# sapflow_v5.net
KiCad netlist of a schematic drawn in EAGLE
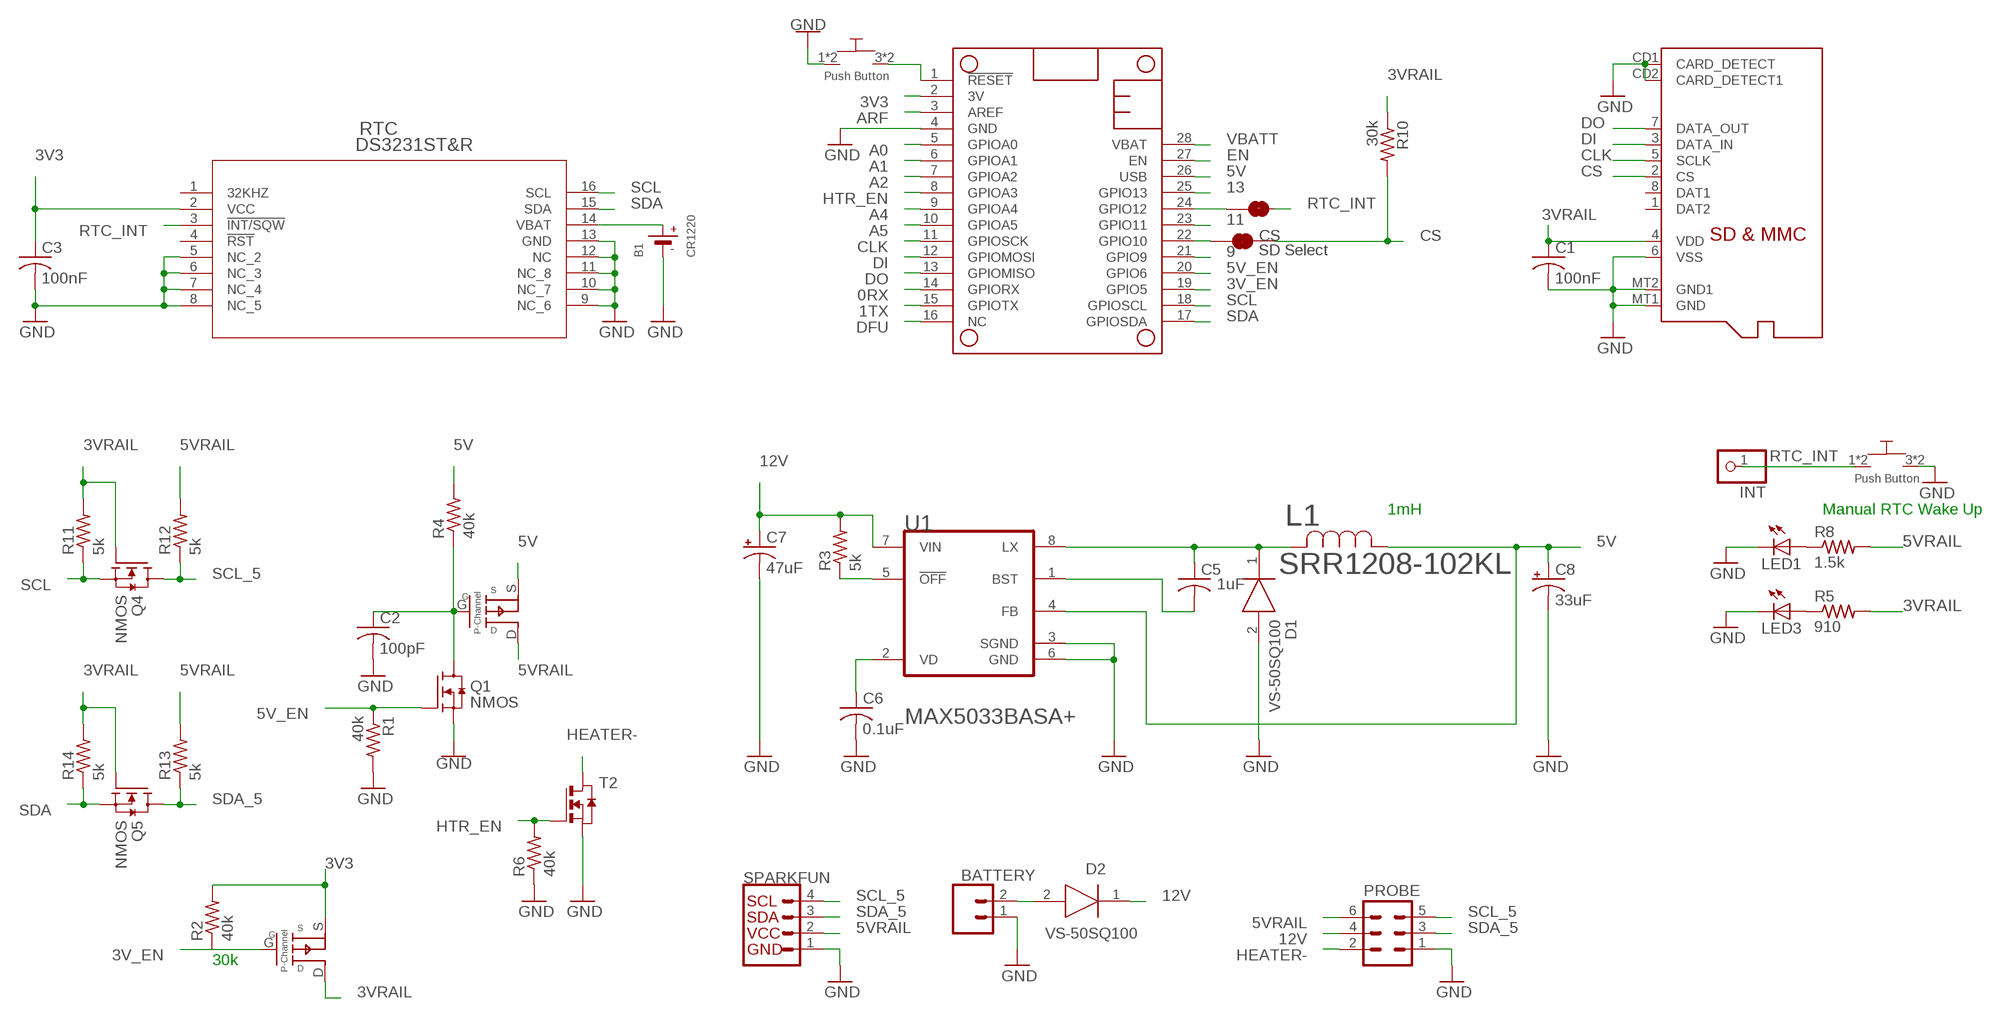
[diagram p0: schematic, sheet 1]

(export (version "E")
  (design (tool "Eeschema 10.0.6"))
  (components
    (comp (ref "B1")
      (value "CR1220")
      (footprint "eagle-import:CR1220")
      (libsource (lib "eagle-import") (part "BATTERYCR1220_SMT"))
    )
    (comp (ref "BATTERY")
      (value "HIGHV-OUT")
      (footprint "eagle-import:1X02_NO_SILK")
      (libsource (lib "eagle-import") (part "CONN_021X02_NO_SILK"))
    )
    (comp (ref "C1")
      (value "100nF")
      (footprint "eagle-import:C0805")
      (libsource (lib "eagle-import") (part "C-USC0805"))
    )
    (comp (ref "C2")
      (value "100pF")
      (footprint "eagle-import:C0805")
      (libsource (lib "eagle-import") (part "resistor_348_C-USC0805"))
    )
    (comp (ref "C3")
      (value "100nF")
      (footprint "eagle-import:C0805")
      (libsource (lib "eagle-import") (part "C-USC0805"))
    )
    (comp (ref "C5")
      (value "1uF")
      (footprint "eagle-import:C0805")
      (libsource (lib "eagle-import") (part "rcl_334_C-USC0805"))
    )
    (comp (ref "C6")
      (value "0.1uF")
      (footprint "eagle-import:C0805")
      (libsource (lib "eagle-import") (part "rcl_334_C-USC0805"))
    )
    (comp (ref "C7")
      (value "47uF")
      (footprint "eagle-import:D_7343-31R")
      (libsource (lib "eagle-import") (part "CPOL-USD/7343-31R"))
    )
    (comp (ref "C8")
      (value "33uF")
      (footprint "eagle-import:D_7343-31R")
      (libsource (lib "eagle-import") (part "CPOL-USD/7343-31R"))
    )
    (comp (ref "CS")
      (value "SD Select")
      (footprint "eagle-import:SMT-JUMPER_2_NC_TRACE_SILK")
      (libsource (lib "eagle-import") (part "JUMPER-SMT_2_NC_TRACE_SILK"))
    )
    (comp (ref "D1")
      (value "VS-50SQ100")
      (footprint "eagle-import:DIOAD1405W86L465D235")
      (fields (field (name "MOUSER_PART_NUMBER") "844-50SQ100") (field (name "RS_PART_NUMBER") "5446041"))
      (libsource (lib "eagle-import") (part "VS-50SQ100"))
    )
    (comp (ref "D2")
      (value "VS-50SQ100")
      (footprint "eagle-import:DIOAD1405W86L465D235")
      (fields (field (name "MOUSER_PART_NUMBER") "844-50SQ100") (field (name "RS_PART_NUMBER") "5446041"))
      (libsource (lib "eagle-import") (part "VS-50SQ100"))
    )
    (comp (ref "INT")
      (value "PINHD-1X1CB")
      (footprint "eagle-import:1X01-CLEANBIG")
      (libsource (lib "eagle-import") (part "PINHD-1X1CB"))
    )
    (comp (ref "L1")
      (value "SRR1208-102KL")
      (footprint "eagle-import:IND_BOURNS_SRR1208")
      (libsource (lib "eagle-import") (part "SRR1208-102KL"))
    )
    (comp (ref "LED1")
      (value "RED")
      (footprint "eagle-import:CHIPLED_0805")
      (libsource (lib "eagle-import") (part "LEDCHIPLED_0805"))
    )
    (comp (ref "LED3")
      (value "RED")
      (footprint "eagle-import:CHIPLED_0805")
      (libsource (lib "eagle-import") (part "LEDCHIPLED_0805"))
    )
    (comp (ref "MICROSD")
      (value "MICROSD")
      (footprint "eagle-import:MICROSD")
      (libsource (lib "eagle-import") (part "MICROSD"))
    )
    (comp (ref "MS2")
      (value "FEATHERWING")
      (footprint "eagle-import:FEATHERWING")
      (libsource (lib "eagle-import") (part "FEATHERWING"))
    )
    (comp (ref "PMOS1")
      (value "SSM3J3228R")
      (footprint "eagle-import:SOT-23-3")
      (libsource (lib "eagle-import") (part "SSM3J3228R"))
    )
    (comp (ref "PMOS2")
      (value "SSM3J3228R")
      (footprint "eagle-import:SOT-23-3")
      (libsource (lib "eagle-import") (part "SSM3J3228R"))
    )
    (comp (ref "PROBE")
      (value "MA03-2")
      (footprint "eagle-import:MA03-2")
      (libsource (lib "eagle-import") (part "MA03-2"))
    )
    (comp (ref "Q1")
      (value "NMOS")
      (footprint "eagle-import:SOT23-S")
      (libsource (lib "eagle-import") (part "NMOS"))
    )
    (comp (ref "Q4")
      (value "NMOS")
      (footprint "eagle-import:SOT23-S")
      (libsource (lib "eagle-import") (part "NMOS"))
    )
    (comp (ref "Q5")
      (value "NMOS")
      (footprint "eagle-import:SOT23-S")
      (libsource (lib "eagle-import") (part "NMOS"))
    )
    (comp (ref "R1")
      (value "40k")
      (footprint "eagle-import:R0805")
      (libsource (lib "eagle-import") (part "R-US_R0805"))
    )
    (comp (ref "R2")
      (value "40k")
      (footprint "eagle-import:R0805")
      (libsource (lib "eagle-import") (part "R-US_R0805"))
    )
    (comp (ref "R3")
      (value "5k")
      (footprint "eagle-import:R0805")
      (libsource (lib "eagle-import") (part "R-US_R0805"))
    )
    (comp (ref "R4")
      (value "40k")
      (footprint "eagle-import:R0805")
      (libsource (lib "eagle-import") (part "R-US_R0805"))
    )
    (comp (ref "R5")
      (value "910")
      (footprint "eagle-import:R0805")
      (libsource (lib "eagle-import") (part "R-US_R0805"))
    )
    (comp (ref "R6")
      (value "40k")
      (footprint "eagle-import:R0805")
      (libsource (lib "eagle-import") (part "R-US_R0805"))
    )
    (comp (ref "R8")
      (value "1.5k")
      (footprint "eagle-import:R0805")
      (libsource (lib "eagle-import") (part "R-US_R0805"))
    )
    (comp (ref "R10")
      (value "30k")
      (footprint "eagle-import:R0805")
      (libsource (lib "eagle-import") (part "R-US_R0805"))
    )
    (comp (ref "R11")
      (value "5k")
      (footprint "eagle-import:R0805")
      (libsource (lib "eagle-import") (part "R-US_R0805"))
    )
    (comp (ref "R12")
      (value "5k")
      (footprint "eagle-import:R0805")
      (libsource (lib "eagle-import") (part "R-US_R0805"))
    )
    (comp (ref "R13")
      (value "5k")
      (footprint "eagle-import:R0805")
      (libsource (lib "eagle-import") (part "R-US_R0805"))
    )
    (comp (ref "R14")
      (value "5k")
      (footprint "eagle-import:R0805")
      (libsource (lib "eagle-import") (part "R-US_R0805"))
    )
    (comp (ref "RTC")
      (value "DS3231ST&R")
      (footprint "eagle-import:21-0042B_16")
      (fields (field (name "MANUFACTURER_PART_NUMBER") "DS3231S#T&R"))
      (libsource (lib "eagle-import") (part "DS3231ST&R"))
    )
    (comp (ref "RTC_INT")
      (value "JUMPER-SMT_2_NC_TRACE_SILK")
      (footprint "eagle-import:SMT-JUMPER_2_NC_TRACE_SILK")
      (libsource (lib "eagle-import") (part "JUMPER-SMT_2_NC_TRACE_SILK"))
    )
    (comp (ref "SPARKFUN")
      (value "I2C_STANDARD_NO_SILK")
      (footprint "eagle-import:1X04_NO_SILK")
      (libsource (lib "eagle-import") (part "I2C_STANDARD_NO_SILK"))
    )
    (comp (ref "T2")
      (value "NMOSSOT223")
      (footprint "eagle-import:SOT223")
      (libsource (lib "eagle-import") (part "NMOSSOT223"))
    )
    (comp (ref "U$1")
      (value "PUSH_BUTTON")
      (footprint "eagle-import:PUSHBUTTON_SMD")
      (libsource (lib "eagle-import") (part "PUSH_BUTTON"))
    )
    (comp (ref "U$2")
      (value "PUSH_BUTTON")
      (footprint "eagle-import:PUSHBUTTON_SMD")
      (libsource (lib "eagle-import") (part "PUSH_BUTTON"))
    )
    (comp (ref "U1")
      (value "MAXIM_MAX5033BASA+MAXIM_MAX5033BASA+_0_1")
      (footprint "eagle-import:MAXIM_MAX5033BASA+_1")
      (fields (field (name "MF") "Maxim") (field (name "MPN") "MAX5033BASA+"))
      (libsource (lib "eagle-import") (part "MAXIM_MAX5033BASA+MAXIM_MAX5033BASA+_0_1"))
    )
  )
  (nets
    (net (code "1") (name "/0RX") (class "Default")
      (node (ref "MS2") (pin "14") (pinfunction "GPIORX_14") (pintype "bidirectional"))
    )
    (net (code "2") (name "/1TX") (class "Default")
      (node (ref "MS2") (pin "15") (pinfunction "GPIOTX_15") (pintype "bidirectional"))
    )
    (net (code "3") (name "/3V3") (class "Default")
      (node (ref "C3") (pin "1") (pinfunction "1_1") (pintype "passive"))
      (node (ref "MS2") (pin "2") (pinfunction "3V_2") (pintype "power_in"))
      (node (ref "PMOS2") (pin "S") (pinfunction "S_S") (pintype "bidirectional"))
      (node (ref "R2") (pin "2") (pinfunction "2_2") (pintype "passive"))
      (node (ref "RTC") (pin "2") (pinfunction "VCC_2") (pintype "power_in"))
    )
    (net (code "4") (name "/3VRAIL") (class "Default")
      (node (ref "C1") (pin "1") (pinfunction "1_1") (pintype "passive"))
      (node (ref "MICROSD") (pin "4") (pinfunction "VDD_4") (pintype "power_in"))
      (node (ref "PMOS2") (pin "D") (pinfunction "D_D") (pintype "bidirectional"))
      (node (ref "Q4") (pin "1") (pinfunction "G_1") (pintype "passive"))
      (node (ref "Q5") (pin "1") (pinfunction "G_1") (pintype "passive"))
      (node (ref "R10") (pin "1") (pinfunction "1_1") (pintype "passive"))
      (node (ref "R11") (pin "2") (pinfunction "2_2") (pintype "passive"))
      (node (ref "R14") (pin "2") (pinfunction "2_2") (pintype "passive"))
      (node (ref "R5") (pin "2") (pinfunction "2_2") (pintype "passive"))
    )
    (net (code "5") (name "/3V_EN") (class "Default")
      (node (ref "MS2") (pin "19") (pinfunction "GPIO5_19") (pintype "bidirectional"))
      (node (ref "PMOS2") (pin "G") (pinfunction "G_G") (pintype "bidirectional"))
      (node (ref "R2") (pin "1") (pinfunction "1_1") (pintype "passive"))
    )
    (net (code "6") (name "/5V") (class "Default")
      (node (ref "C8") (pin "+") (pinfunction "+_+") (pintype "passive"))
      (node (ref "L1") (pin "1") (pinfunction "1_1") (pintype "passive"))
      (node (ref "MS2") (pin "26") (pinfunction "USB_26") (pintype "power_in"))
      (node (ref "PMOS1") (pin "S") (pinfunction "S_S") (pintype "bidirectional"))
      (node (ref "R4") (pin "2") (pinfunction "2_2") (pintype "passive"))
      (node (ref "U1") (pin "4") (pinfunction "FB_4") (pintype "input"))
    )
    (net (code "7") (name "/5VRAIL") (class "Default")
      (node (ref "PMOS1") (pin "D") (pinfunction "D_D") (pintype "bidirectional"))
      (node (ref "PROBE") (pin "6") (pinfunction "6_6") (pintype "passive"))
      (node (ref "R12") (pin "2") (pinfunction "2_2") (pintype "passive"))
      (node (ref "R13") (pin "2") (pinfunction "2_2") (pintype "passive"))
      (node (ref "R8") (pin "2") (pinfunction "2_2") (pintype "passive"))
      (node (ref "SPARKFUN") (pin "2") (pinfunction "VCC_2") (pintype "power_in"))
    )
    (net (code "8") (name "/5V_EN") (class "Default")
      (node (ref "MS2") (pin "20") (pinfunction "GPIO6_20") (pintype "bidirectional"))
      (node (ref "Q1") (pin "1") (pinfunction "G_1") (pintype "passive"))
      (node (ref "R1") (pin "1") (pinfunction "1_1") (pintype "passive"))
    )
    (net (code "9") (name "/9") (class "Default")
      (node (ref "MS2") (pin "21") (pinfunction "GPIO9_21") (pintype "bidirectional"))
    )
    (net (code "10") (name "/11") (class "Default")
      (node (ref "MS2") (pin "23") (pinfunction "GPIO11_23") (pintype "bidirectional"))
    )
    (net (code "11") (name "/12V") (class "Default")
      (node (ref "C7") (pin "+") (pinfunction "+_+") (pintype "passive"))
      (node (ref "D2") (pin "1") (pinfunction "K_1") (pintype "bidirectional"))
      (node (ref "PROBE") (pin "4") (pinfunction "4_4") (pintype "passive"))
      (node (ref "R3") (pin "2") (pinfunction "2_2") (pintype "passive"))
      (node (ref "U1") (pin "7") (pinfunction "VIN_7") (pintype "power_in"))
    )
    (net (code "12") (name "/13") (class "Default")
      (node (ref "MS2") (pin "25") (pinfunction "GPIO13_25") (pintype "bidirectional"))
    )
    (net (code "13") (name "/A0") (class "Default")
      (node (ref "MS2") (pin "5") (pinfunction "GPIOA0_5") (pintype "bidirectional"))
    )
    (net (code "14") (name "/A1") (class "Default")
      (node (ref "MS2") (pin "6") (pinfunction "GPIOA1_6") (pintype "bidirectional"))
    )
    (net (code "15") (name "/A2") (class "Default")
      (node (ref "MS2") (pin "7") (pinfunction "GPIOA2_7") (pintype "bidirectional"))
    )
    (net (code "16") (name "/A4") (class "Default")
      (node (ref "MS2") (pin "9") (pinfunction "GPIOA4_9") (pintype "bidirectional"))
    )
    (net (code "17") (name "/A5") (class "Default")
      (node (ref "MS2") (pin "10") (pinfunction "GPIOA5_10") (pintype "bidirectional"))
    )
    (net (code "18") (name "/ARF") (class "Default")
      (node (ref "MS2") (pin "3") (pinfunction "AREF_3") (pintype "passive"))
    )
    (net (code "19") (name "/CLK") (class "Default")
      (node (ref "MICROSD") (pin "5") (pinfunction "SCLK_5") (pintype "input"))
      (node (ref "MS2") (pin "11") (pinfunction "GPIOSCK_11") (pintype "bidirectional"))
    )
    (net (code "20") (name "/CS") (class "Default")
      (node (ref "CS") (pin "2") (pinfunction "2_2") (pintype "passive"))
      (node (ref "MICROSD") (pin "2") (pinfunction "CS_2") (pintype "input"))
      (node (ref "R10") (pin "2") (pinfunction "2_2") (pintype "passive"))
    )
    (net (code "21") (name "/DFU") (class "Default")
      (node (ref "MS2") (pin "16") (pinfunction "NC_16") (pintype "passive"))
    )
    (net (code "22") (name "/DI") (class "Default")
      (node (ref "MICROSD") (pin "3") (pinfunction "DATA_IN_3") (pintype "input"))
      (node (ref "MS2") (pin "12") (pinfunction "GPIOMOSI_12") (pintype "bidirectional"))
    )
    (net (code "23") (name "/DO") (class "Default")
      (node (ref "MICROSD") (pin "7") (pinfunction "DATA_OUT_7") (pintype "output"))
      (node (ref "MS2") (pin "13") (pinfunction "GPIOMISO_13") (pintype "bidirectional"))
    )
    (net (code "24") (name "/EN") (class "Default")
      (node (ref "MS2") (pin "27") (pinfunction "EN_27") (pintype "passive"))
    )
    (net (code "25") (name "/HEATER-") (class "Default")
      (node (ref "PROBE") (pin "2") (pinfunction "2_2") (pintype "passive"))
      (node (ref "T2") (pin "2") (pinfunction "D_2") (pintype "passive"))
      (node (ref "T2") (pin "4") (pinfunction "D_4") (pintype "passive"))
    )
    (net (code "26") (name "/HTR_EN") (class "Default")
      (node (ref "MS2") (pin "8") (pinfunction "GPIOA3_8") (pintype "bidirectional"))
      (node (ref "R6") (pin "2") (pinfunction "2_2") (pintype "passive"))
      (node (ref "T2") (pin "1") (pinfunction "G_1") (pintype "passive"))
    )
    (net (code "27") (name "/RTC_INT") (class "Default")
      (node (ref "INT") (pin "1") (pinfunction "1_1") (pintype "passive"))
      (node (ref "RTC") (pin "3") (pinfunction "~{INT/SQW}_3") (pintype "passive"))
      (node (ref "RTC_INT") (pin "2") (pinfunction "2_2") (pintype "passive"))
      (node (ref "U$2") (pin "1") (pinfunction "P$1_1") (pintype "bidirectional"))
      (node (ref "U$2") (pin "2") (pinfunction "P$1_2") (pintype "bidirectional"))
    )
    (net (code "28") (name "/SCL") (class "Default")
      (node (ref "MS2") (pin "18") (pinfunction "GPIOSCL_18") (pintype "bidirectional"))
      (node (ref "Q4") (pin "2") (pinfunction "S_2") (pintype "passive"))
      (node (ref "R11") (pin "1") (pinfunction "1_1") (pintype "passive"))
      (node (ref "RTC") (pin "16") (pinfunction "SCL_16") (pintype "passive"))
    )
    (net (code "29") (name "/SCL_5") (class "Default")
      (node (ref "PROBE") (pin "5") (pinfunction "5_5") (pintype "passive"))
      (node (ref "Q4") (pin "3") (pinfunction "D_3") (pintype "passive"))
      (node (ref "R12") (pin "1") (pinfunction "1_1") (pintype "passive"))
      (node (ref "SPARKFUN") (pin "4") (pinfunction "SCL_4") (pintype "passive"))
    )
    (net (code "30") (name "/SDA") (class "Default")
      (node (ref "MS2") (pin "17") (pinfunction "GPIOSDA_17") (pintype "bidirectional"))
      (node (ref "Q5") (pin "2") (pinfunction "S_2") (pintype "passive"))
      (node (ref "R14") (pin "1") (pinfunction "1_1") (pintype "passive"))
      (node (ref "RTC") (pin "15") (pinfunction "SDA_15") (pintype "passive"))
    )
    (net (code "31") (name "/SDA_5") (class "Default")
      (node (ref "PROBE") (pin "3") (pinfunction "3_3") (pintype "passive"))
      (node (ref "Q5") (pin "3") (pinfunction "D_3") (pintype "passive"))
      (node (ref "R13") (pin "1") (pinfunction "1_1") (pintype "passive"))
      (node (ref "SPARKFUN") (pin "3") (pinfunction "SDA_3") (pintype "passive"))
    )
    (net (code "32") (name "/VBATT") (class "Default")
      (node (ref "MS2") (pin "28") (pinfunction "VBAT_28") (pintype "power_in"))
    )
    (net (code "33") (name "GND") (class "Default")
      (node (ref "B1") (pin "-") (pinfunction "-_-") (pintype "passive"))
      (node (ref "BATTERY") (pin "1") (pinfunction "1_1") (pintype "passive"))
      (node (ref "C1") (pin "2") (pinfunction "2_2") (pintype "passive"))
      (node (ref "C2") (pin "2") (pinfunction "2_2") (pintype "passive"))
      (node (ref "C3") (pin "2") (pinfunction "2_2") (pintype "passive"))
      (node (ref "C6") (pin "2") (pinfunction "2_2") (pintype "passive"))
      (node (ref "C7") (pin "-") (pinfunction "-_-") (pintype "passive"))
      (node (ref "C8") (pin "-") (pinfunction "-_-") (pintype "passive"))
      (node (ref "D1") (pin "2") (pinfunction "A_2") (pintype "bidirectional"))
      (node (ref "LED1") (pin "C") (pinfunction "C_C") (pintype "passive"))
      (node (ref "LED3") (pin "C") (pinfunction "C_C") (pintype "passive"))
      (node (ref "MICROSD") (pin "6") (pinfunction "VSS_6") (pintype "power_in"))
      (node (ref "MICROSD") (pin "CD1") (pinfunction "CARD_DETECT_CD1") (pintype "passive"))
      (node (ref "MICROSD") (pin "CD2") (pinfunction "CARD_DETECT1_CD2") (pintype "passive"))
      (node (ref "MICROSD") (pin "MT1") (pinfunction "GND_MT1") (pintype "power_in"))
      (node (ref "MICROSD") (pin "MT2") (pinfunction "GND1_MT2") (pintype "power_in"))
      (node (ref "MS2") (pin "4") (pinfunction "GND_4") (pintype "power_in"))
      (node (ref "PROBE") (pin "1") (pinfunction "1_1") (pintype "passive"))
      (node (ref "Q1") (pin "2") (pinfunction "S_2") (pintype "passive"))
      (node (ref "R1") (pin "2") (pinfunction "2_2") (pintype "passive"))
      (node (ref "R6") (pin "1") (pinfunction "1_1") (pintype "passive"))
      (node (ref "RTC") (pin "10") (pinfunction "NC_7_10") (pintype "passive"))
      (node (ref "RTC") (pin "11") (pinfunction "NC_8_11") (pintype "passive"))
      (node (ref "RTC") (pin "12") (pinfunction "NC_12") (pintype "passive"))
      (node (ref "RTC") (pin "13") (pinfunction "GND_13") (pintype "power_in"))
      (node (ref "RTC") (pin "5") (pinfunction "NC_2_5") (pintype "passive"))
      (node (ref "RTC") (pin "6") (pinfunction "NC_3_6") (pintype "passive"))
      (node (ref "RTC") (pin "7") (pinfunction "NC_4_7") (pintype "passive"))
      (node (ref "RTC") (pin "8") (pinfunction "NC_5_8") (pintype "passive"))
      (node (ref "RTC") (pin "9") (pinfunction "NC_6_9") (pintype "passive"))
      (node (ref "SPARKFUN") (pin "1") (pinfunction "GND_1") (pintype "power_in"))
      (node (ref "T2") (pin "3") (pinfunction "S_3") (pintype "passive"))
      (node (ref "U$1") (pin "1") (pinfunction "P$1_1") (pintype "bidirectional"))
      (node (ref "U$1") (pin "2") (pinfunction "P$1_2") (pintype "bidirectional"))
      (node (ref "U$2") (pin "3") (pinfunction "P$2_3") (pintype "bidirectional"))
      (node (ref "U$2") (pin "4") (pinfunction "P$2_4") (pintype "bidirectional"))
      (node (ref "U1") (pin "3") (pinfunction "SGND_3") (pintype "power_in"))
      (node (ref "U1") (pin "6") (pinfunction "GND_6") (pintype "power_in"))
    )
    (net (code "34") (name "Net-(B1-+)") (class "Default")
      (node (ref "B1") (pin "+$1") (pinfunction "+_+$1") (pintype "passive"))
      (node (ref "RTC") (pin "14") (pinfunction "VBAT_14") (pintype "power_in"))
    )
    (net (code "35") (name "Net-(D1-K)") (class "Default")
      (node (ref "C5") (pin "1") (pinfunction "1_1") (pintype "passive"))
      (node (ref "D1") (pin "1") (pinfunction "K_1") (pintype "bidirectional"))
      (node (ref "L1") (pin "2") (pinfunction "2_2") (pintype "passive"))
      (node (ref "U1") (pin "8") (pinfunction "LX_8") (pintype "passive"))
    )
    (net (code "36") (name "Net-(D2-A)") (class "Default")
      (node (ref "BATTERY") (pin "2") (pinfunction "2_2") (pintype "passive"))
      (node (ref "D2") (pin "2") (pinfunction "A_2") (pintype "bidirectional"))
    )
    (net (code "37") (name "Net-(LED1-PadA)") (class "Default")
      (node (ref "LED1") (pin "A") (pinfunction "A_A") (pintype "passive"))
      (node (ref "R8") (pin "1") (pinfunction "1_1") (pintype "passive"))
    )
    (net (code "38") (name "Net-(LED3-PadA)") (class "Default")
      (node (ref "LED3") (pin "A") (pinfunction "A_A") (pintype "passive"))
      (node (ref "R5") (pin "1") (pinfunction "1_1") (pintype "passive"))
    )
    (net (code "39") (name "Net-(MS2-GPIO10)") (class "Default")
      (node (ref "CS") (pin "1") (pinfunction "1_1") (pintype "passive"))
      (node (ref "MS2") (pin "22") (pinfunction "GPIO10_22") (pintype "bidirectional"))
    )
    (net (code "40") (name "Net-(MS2-GPIO12)") (class "Default")
      (node (ref "MS2") (pin "24") (pinfunction "GPIO12_24") (pintype "bidirectional"))
      (node (ref "RTC_INT") (pin "1") (pinfunction "1_1") (pintype "passive"))
    )
    (net (code "41") (name "Net-(MS2-~{RESET})") (class "Default")
      (node (ref "MS2") (pin "1") (pinfunction "~{RESET}_1") (pintype "input"))
      (node (ref "U$1") (pin "3") (pinfunction "P$2_3") (pintype "bidirectional"))
      (node (ref "U$1") (pin "4") (pinfunction "P$2_4") (pintype "bidirectional"))
    )
    (net (code "42") (name "Net-(Q1-D)") (class "Default")
      (node (ref "C2") (pin "1") (pinfunction "1_1") (pintype "passive"))
      (node (ref "PMOS1") (pin "G") (pinfunction "G_G") (pintype "bidirectional"))
      (node (ref "Q1") (pin "3") (pinfunction "D_3") (pintype "passive"))
      (node (ref "R4") (pin "1") (pinfunction "1_1") (pintype "passive"))
    )
    (net (code "43") (name "Net-(U1-BST)") (class "Default")
      (node (ref "C5") (pin "2") (pinfunction "2_2") (pintype "passive"))
      (node (ref "U1") (pin "1") (pinfunction "BST_1") (pintype "passive"))
    )
    (net (code "44") (name "Net-(U1-VD)") (class "Default")
      (node (ref "C6") (pin "1") (pinfunction "1_1") (pintype "passive"))
      (node (ref "U1") (pin "2") (pinfunction "VD_2") (pintype "power_in"))
    )
    (net (code "45") (name "Net-(U1-~{OFF})") (class "Default")
      (node (ref "R3") (pin "1") (pinfunction "1_1") (pintype "passive"))
      (node (ref "U1") (pin "5") (pinfunction "~{OFF}_5") (pintype "input"))
    )
    (net (code "46") (name "unconnected-(MICROSD-DAT1-Pad8)") (class "Default")
      (node (ref "MICROSD") (pin "8") (pinfunction "DAT1_8") (pintype "bidirectional"))
    )
    (net (code "47") (name "unconnected-(MICROSD-DAT2-Pad1)") (class "Default")
      (node (ref "MICROSD") (pin "1") (pinfunction "DAT2_1") (pintype "bidirectional"))
    )
    (net (code "48") (name "unconnected-(RTC-32KHZ-Pad1)") (class "Default")
      (node (ref "RTC") (pin "1") (pinfunction "32KHZ_1") (pintype "passive"))
    )
    (net (code "49") (name "unconnected-(RTC-~{RST}-Pad4)") (class "Default")
      (node (ref "RTC") (pin "4") (pinfunction "~{RST}_4") (pintype "passive"))
    )
  )
)
